# PLnew.net
KiCad netlist of a schematic drawn in EAGLE
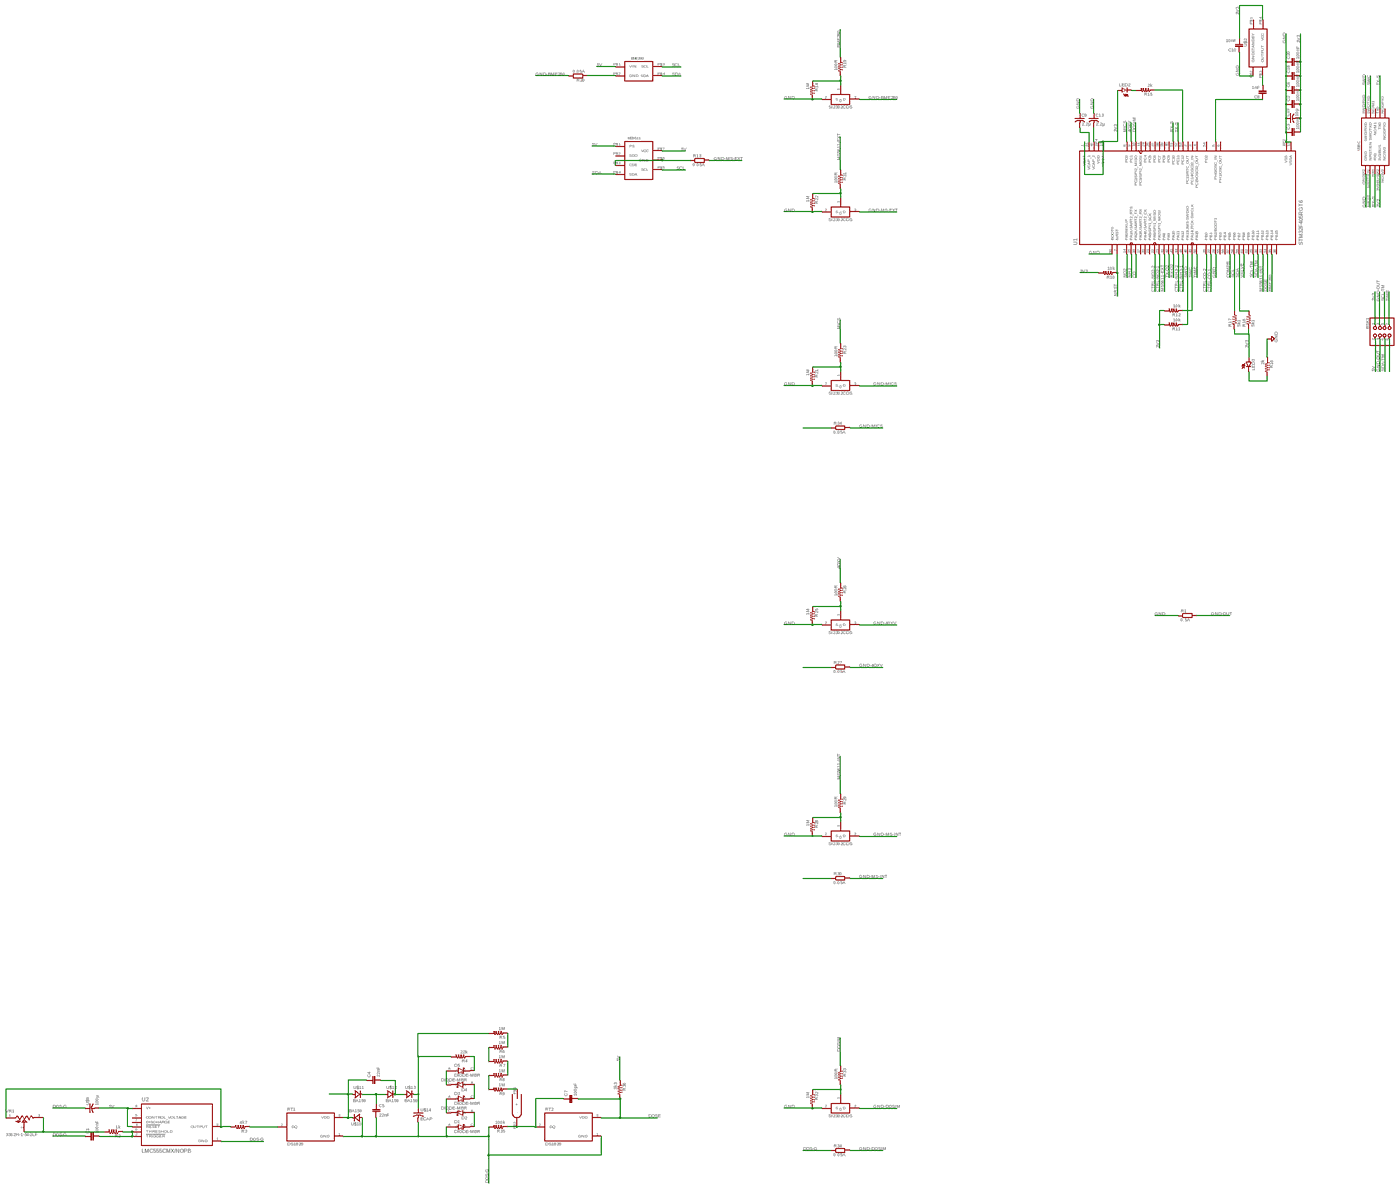
[diagram p0: schematic, sheet 1, overview]
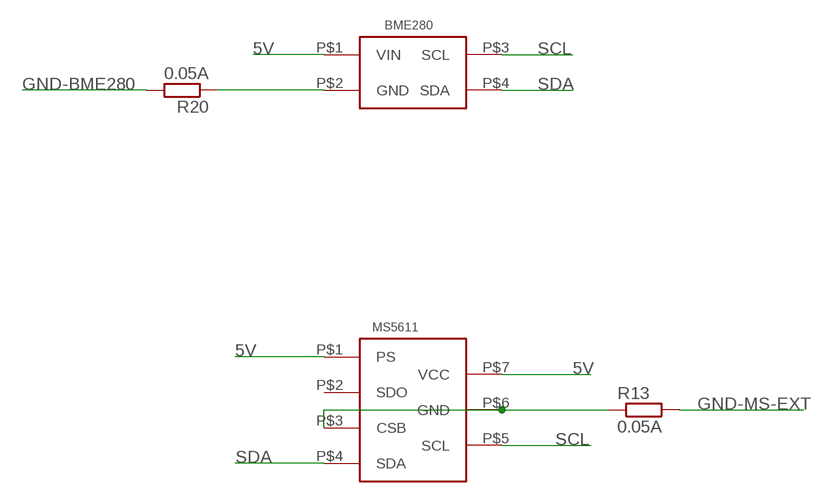
[diagram p1: schematic, sheet 1, part 1 of 4]
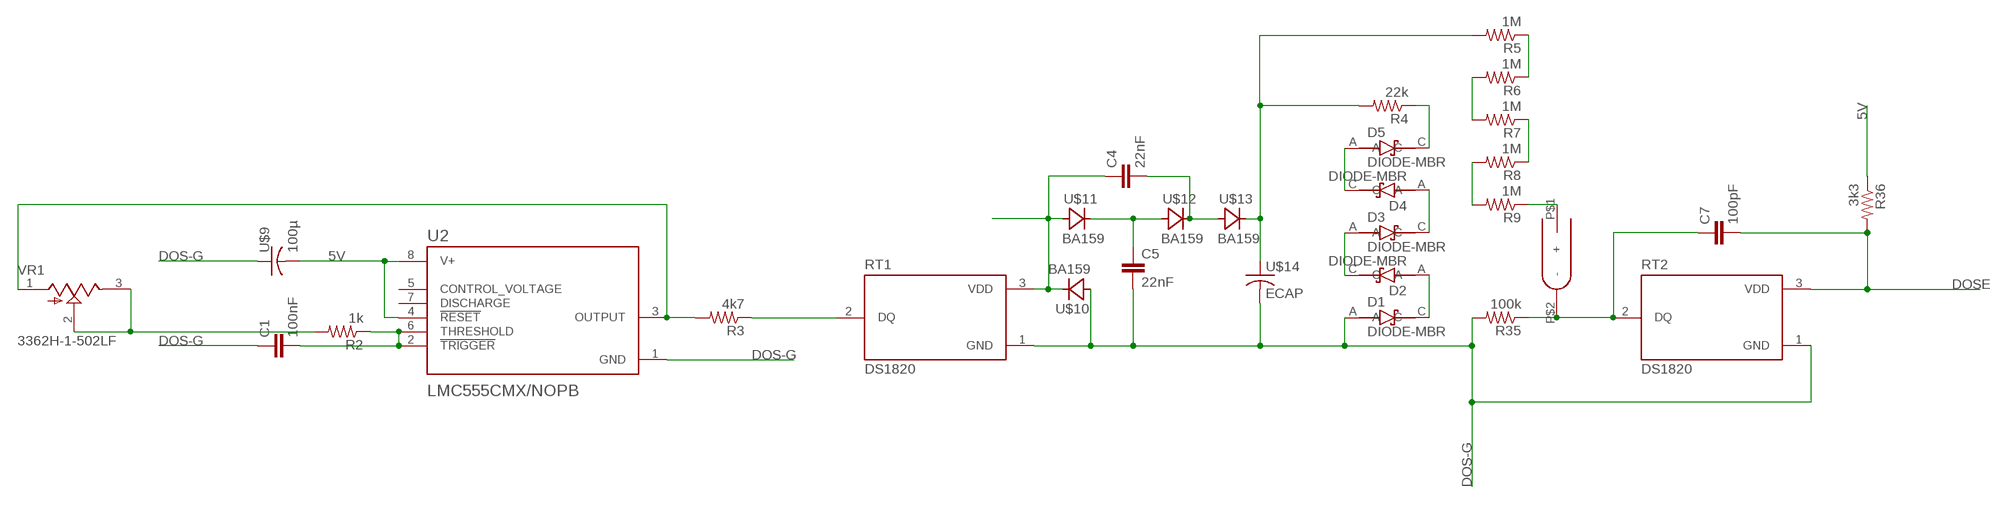
[diagram p2: schematic, sheet 1, part 2 of 4]
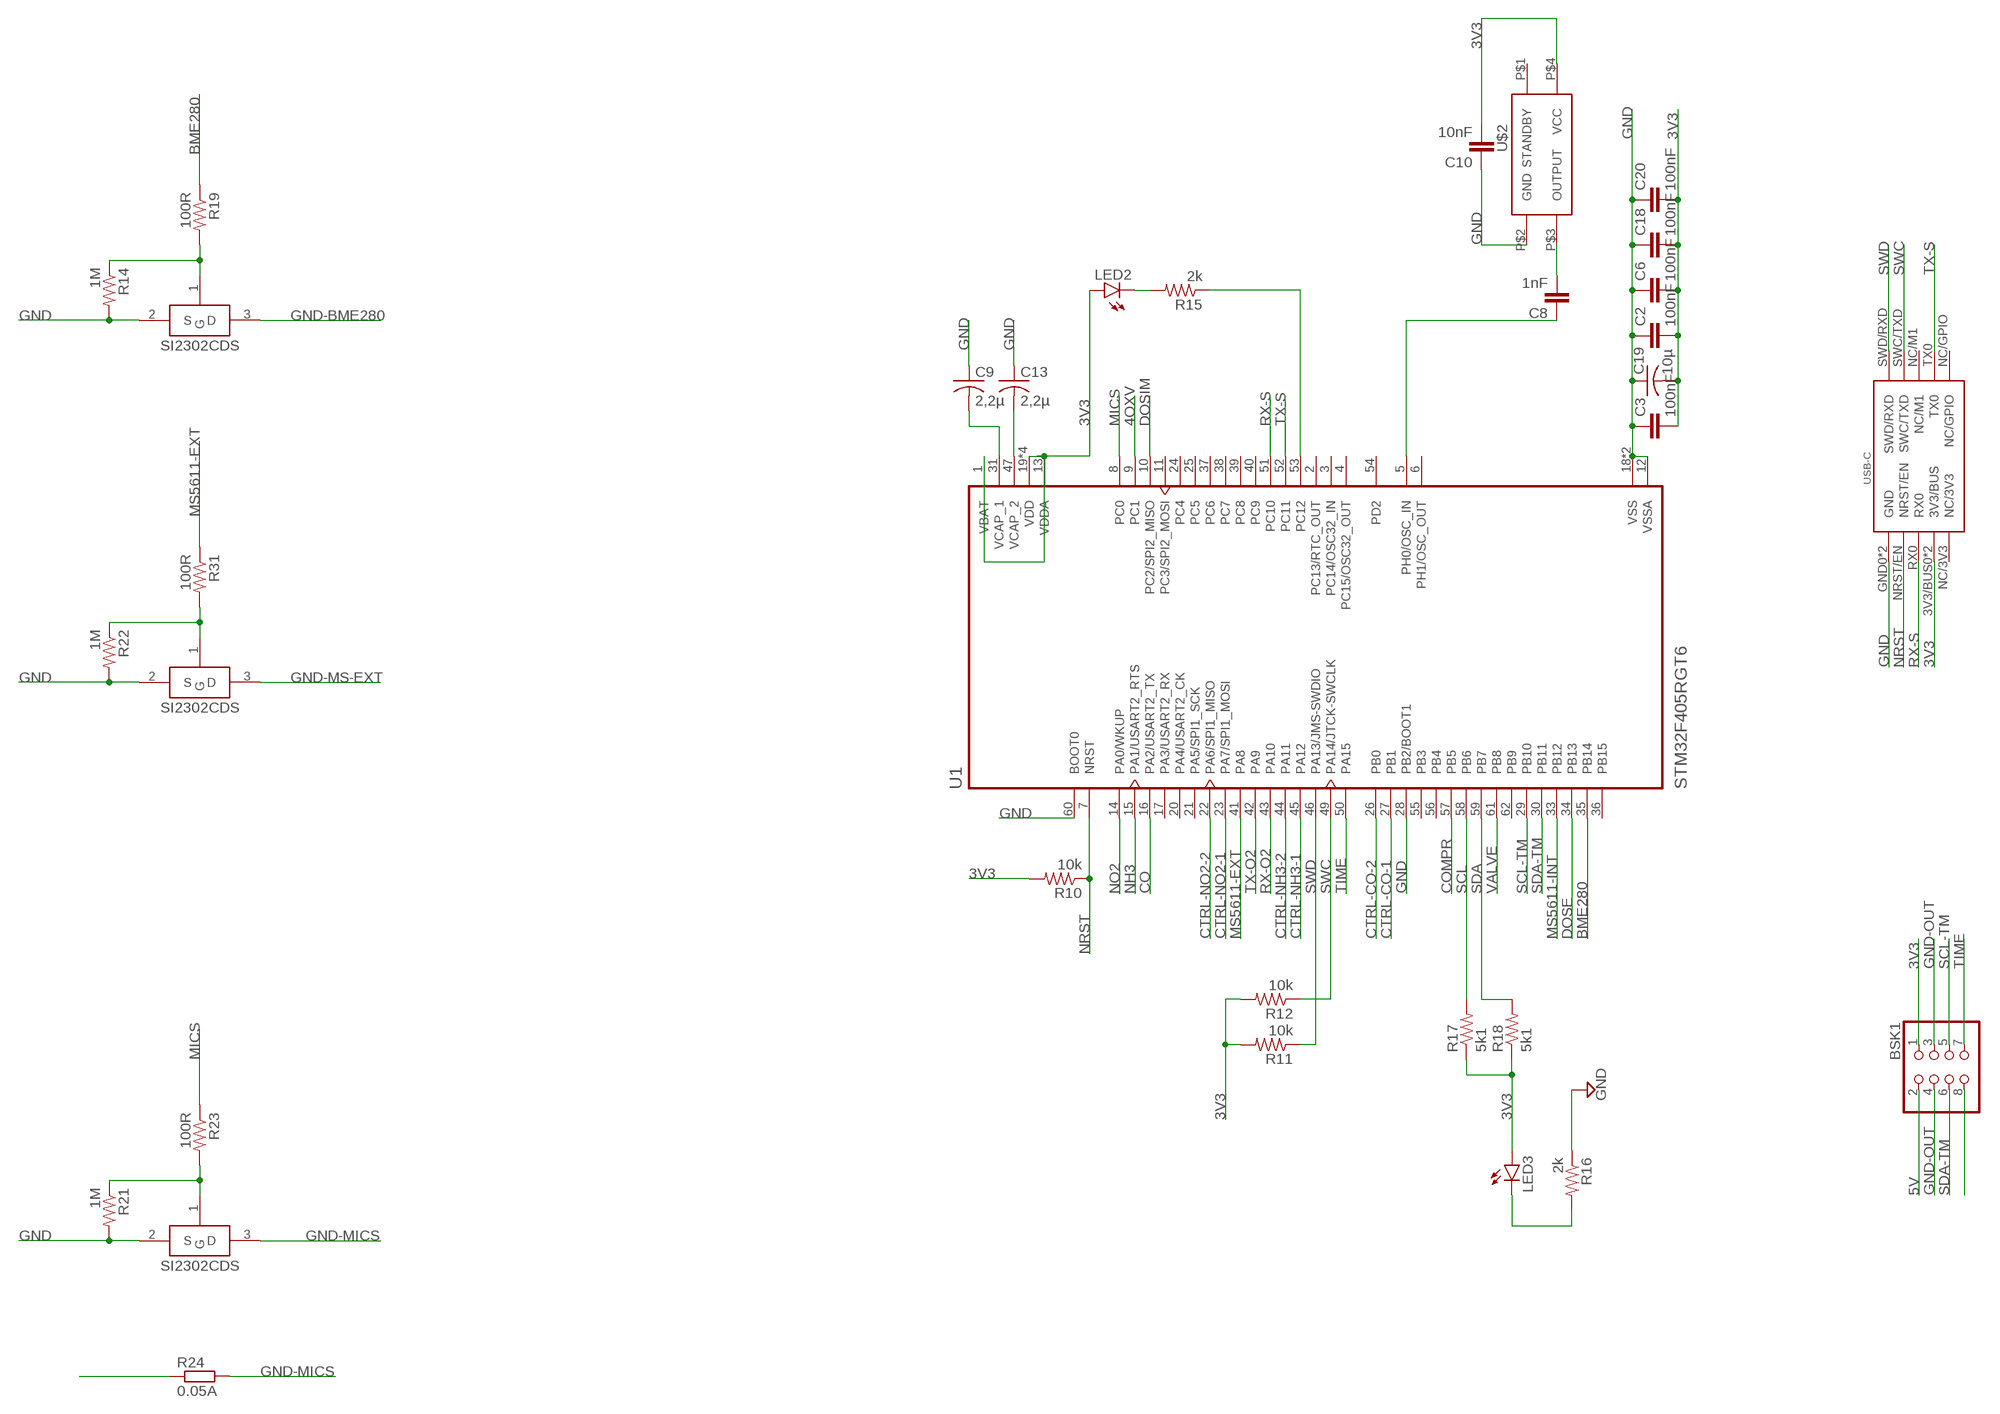
[diagram p3: schematic, sheet 1, part 3 of 4]
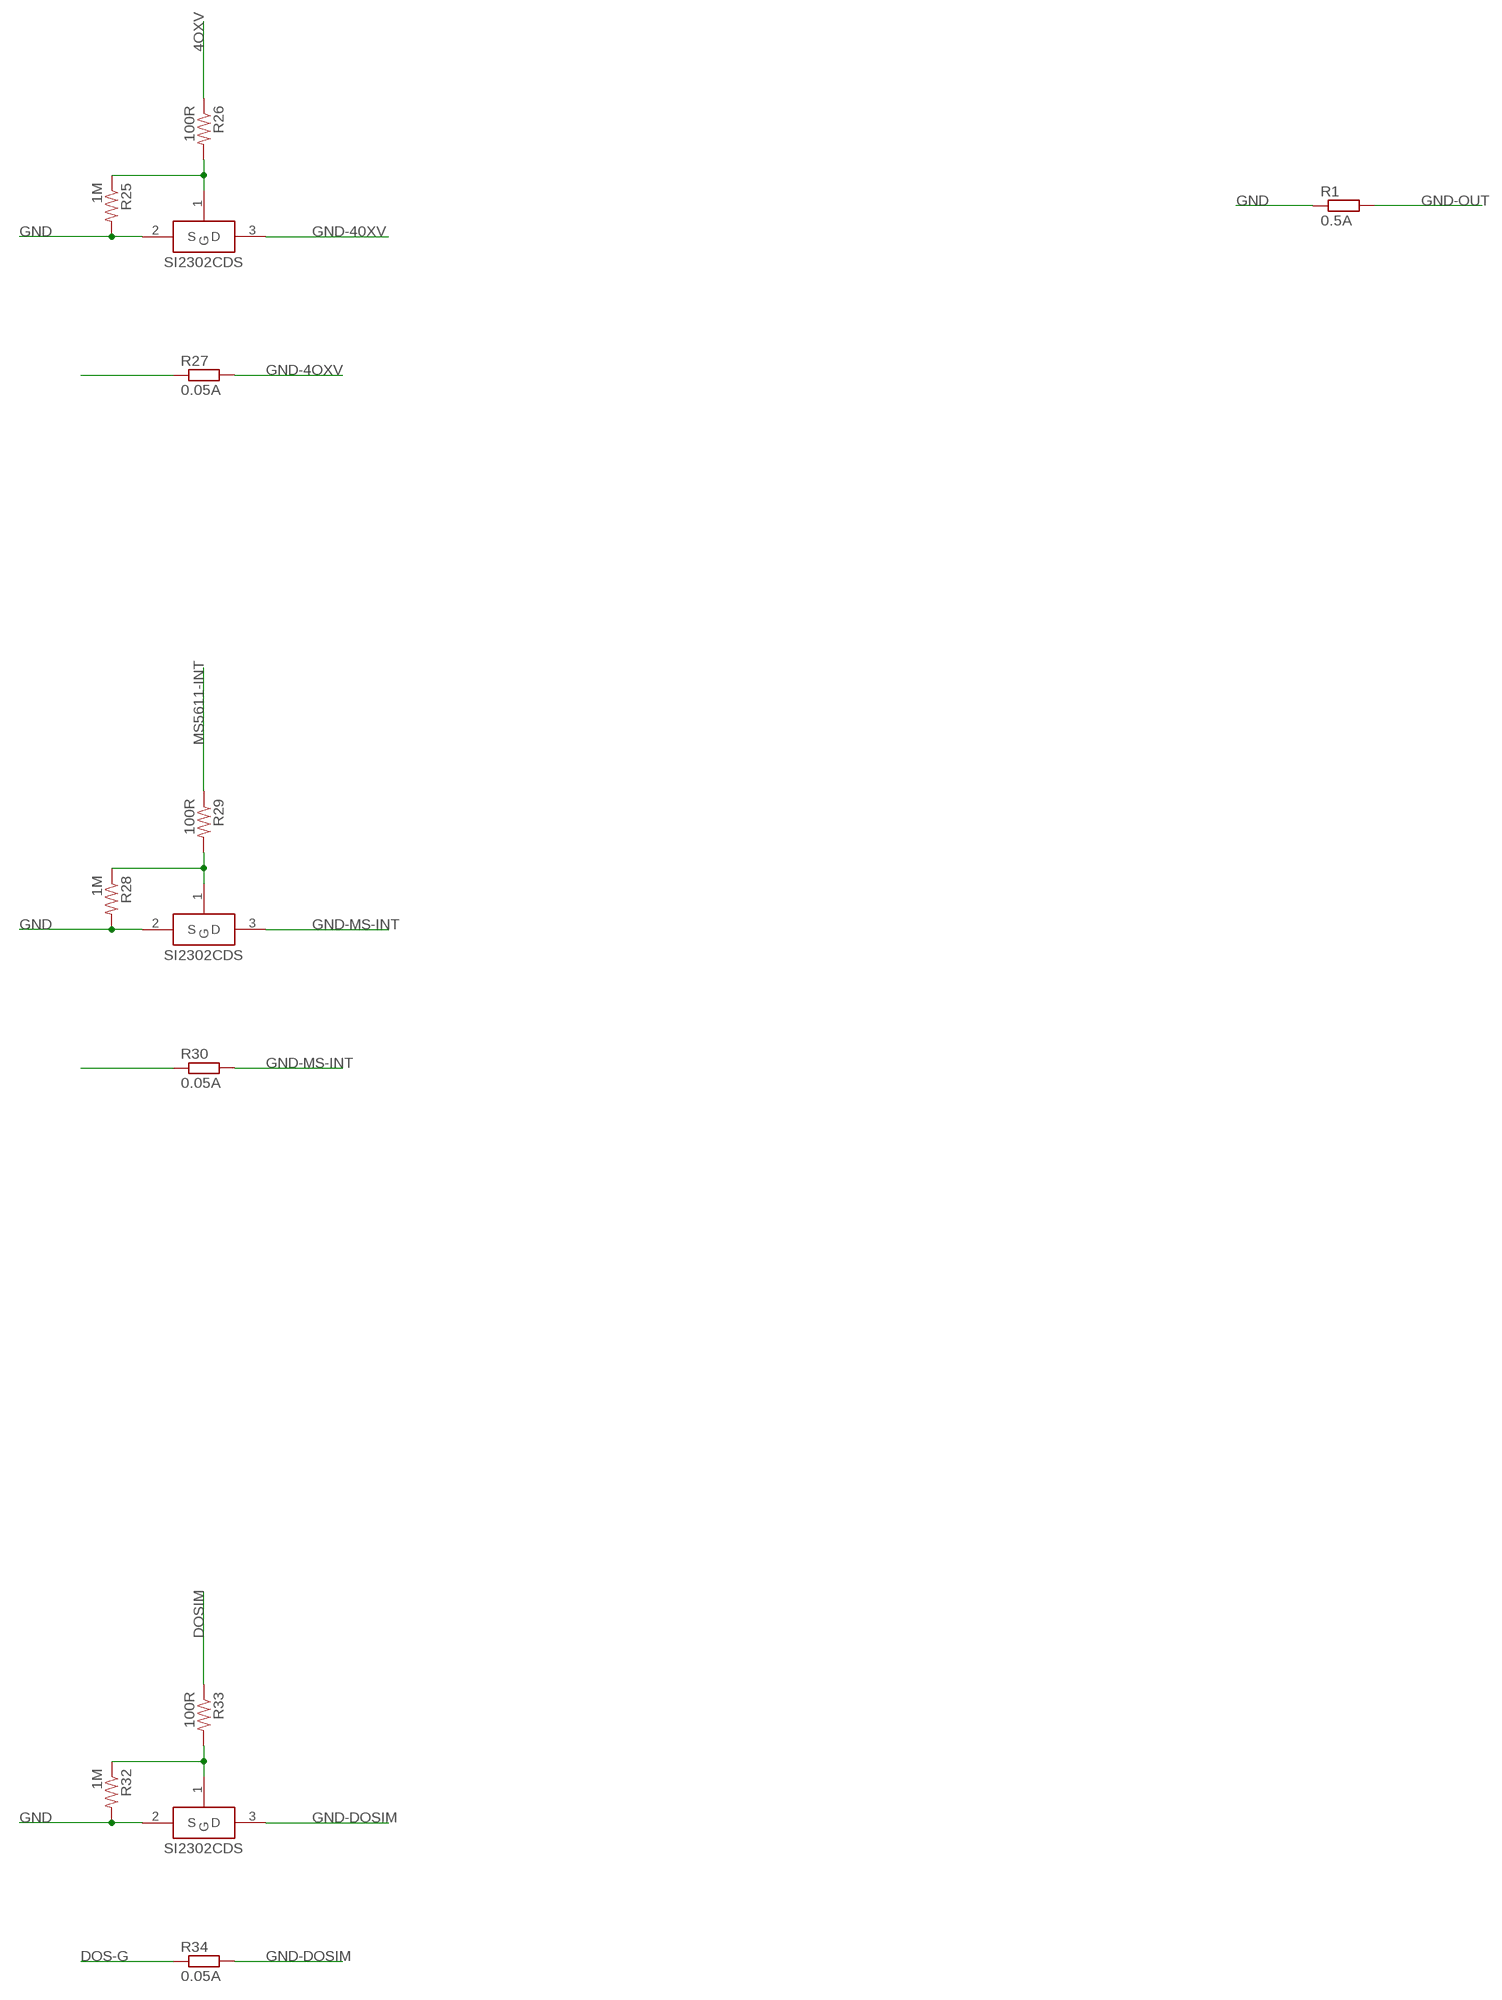
[diagram p4: schematic, sheet 1, part 4 of 4]

(export (version "E")
  (design (tool "Eeschema 10.0.6"))
  (components
    (comp (ref "BME280")
      (value "BME280")
      (footprint "eagle-import:BME280")
      (libsource (lib "eagle-import") (part "BME280"))
    )
    (comp (ref "BSK1")
      (value "PINHD-2X4")
      (footprint "eagle-import:2X04")
      (libsource (lib "eagle-import") (part "PINHD-2X4"))
    )
    (comp (ref "C1")
      (value "100nF")
      (footprint "eagle-import:C0603")
      (libsource (lib "eagle-import") (part "C-EUC0603"))
    )
    (comp (ref "C2")
      (value "100nF")
      (footprint "eagle-import:C0603")
      (libsource (lib "eagle-import") (part "C-EUC0603"))
    )
    (comp (ref "C3")
      (value "100nF")
      (footprint "eagle-import:C0603")
      (libsource (lib "eagle-import") (part "C-EUC0603"))
    )
    (comp (ref "C4")
      (value "22nF")
      (footprint "eagle-import:C1210")
      (libsource (lib "eagle-import") (part "C-EUC1210"))
    )
    (comp (ref "C5")
      (value "22nF")
      (footprint "eagle-import:C1210")
      (libsource (lib "eagle-import") (part "C-EUC1210"))
    )
    (comp (ref "C6")
      (value "100nF")
      (footprint "eagle-import:C0603")
      (libsource (lib "eagle-import") (part "C-EUC0603"))
    )
    (comp (ref "C7")
      (value "100pF")
      (footprint "eagle-import:C0603")
      (libsource (lib "eagle-import") (part "C-EUC0603"))
    )
    (comp (ref "C8")
      (value "1nF")
      (footprint "eagle-import:C0603")
      (libsource (lib "eagle-import") (part "C-EUC0603"))
    )
    (comp (ref "C9")
      (value "2,2µ")
      (footprint "eagle-import:C0603")
      (libsource (lib "eagle-import") (part "C-USC0603"))
    )
    (comp (ref "C10")
      (value "10nF")
      (footprint "eagle-import:C0603")
      (libsource (lib "eagle-import") (part "C-EUC0603"))
    )
    (comp (ref "C13")
      (value "2,2µ")
      (footprint "eagle-import:C0603")
      (libsource (lib "eagle-import") (part "C-USC0603"))
    )
    (comp (ref "C18")
      (value "100nF")
      (footprint "eagle-import:C0603")
      (libsource (lib "eagle-import") (part "C-EUC0603"))
    )
    (comp (ref "C19")
      (value "10µ")
      (footprint "eagle-import:C1206")
      (libsource (lib "eagle-import") (part "C-USC1206"))
    )
    (comp (ref "C20")
      (value "100nF")
      (footprint "eagle-import:C0603")
      (libsource (lib "eagle-import") (part "C-EUC0603"))
    )
    (comp (ref "D1")
      (value "DIODE-MBR")
      (footprint "eagle-import:SOD123")
      (fields (field (name "MF") "ON Semiconductor") (field (name "MP") "MBR0520LT1G"))
      (libsource (lib "eagle-import") (part "DIODE-MBR"))
    )
    (comp (ref "D2")
      (value "DIODE-MBR")
      (footprint "eagle-import:SOD123")
      (fields (field (name "MF") "ON Semiconductor") (field (name "MP") "MBR0520LT1G"))
      (libsource (lib "eagle-import") (part "DIODE-MBR"))
    )
    (comp (ref "D3")
      (value "DIODE-MBR")
      (footprint "eagle-import:SOD123")
      (fields (field (name "MF") "ON Semiconductor") (field (name "MP") "MBR0520LT1G"))
      (libsource (lib "eagle-import") (part "DIODE-MBR"))
    )
    (comp (ref "D4")
      (value "DIODE-MBR")
      (footprint "eagle-import:SOD123")
      (fields (field (name "MF") "ON Semiconductor") (field (name "MP") "MBR0520LT1G"))
      (libsource (lib "eagle-import") (part "DIODE-MBR"))
    )
    (comp (ref "D5")
      (value "DIODE-MBR")
      (footprint "eagle-import:SOD123")
      (fields (field (name "MF") "ON Semiconductor") (field (name "MP") "MBR0520LT1G"))
      (libsource (lib "eagle-import") (part "DIODE-MBR"))
    )
    (comp (ref "LED2")
      (value "LEDCHIPLED_0603")
      (footprint "eagle-import:CHIPLED_0603")
      (libsource (lib "eagle-import") (part "LEDCHIPLED_0603"))
    )
    (comp (ref "LED3")
      (value "LEDCHIPLED_0603")
      (footprint "eagle-import:CHIPLED_0603")
      (libsource (lib "eagle-import") (part "LEDCHIPLED_0603"))
    )
    (comp (ref "R1")
      (value "0.5A")
      (footprint "eagle-import:R1210")
      (libsource (lib "eagle-import") (part "R-EU_R1210"))
    )
    (comp (ref "R2")
      (value "1k")
      (footprint "eagle-import:R0603")
      (libsource (lib "eagle-import") (part "R-US_R0603"))
    )
    (comp (ref "R3")
      (value "4k7")
      (footprint "eagle-import:R0603")
      (libsource (lib "eagle-import") (part "R-US_R0603"))
    )
    (comp (ref "R4")
      (value "22k")
      (footprint "eagle-import:R0603")
      (libsource (lib "eagle-import") (part "R-US_R0603"))
    )
    (comp (ref "R5")
      (value "1M")
      (footprint "eagle-import:R0603")
      (libsource (lib "eagle-import") (part "R-US_R0603"))
    )
    (comp (ref "R6")
      (value "1M")
      (footprint "eagle-import:R0603")
      (libsource (lib "eagle-import") (part "R-US_R0603"))
    )
    (comp (ref "R7")
      (value "1M")
      (footprint "eagle-import:R0603")
      (libsource (lib "eagle-import") (part "R-US_R0603"))
    )
    (comp (ref "R8")
      (value "1M")
      (footprint "eagle-import:R0603")
      (libsource (lib "eagle-import") (part "R-US_R0603"))
    )
    (comp (ref "R9")
      (value "1M")
      (footprint "eagle-import:R0603")
      (libsource (lib "eagle-import") (part "R-US_R0603"))
    )
    (comp (ref "R10")
      (value "10k")
      (footprint "eagle-import:R0603")
      (libsource (lib "eagle-import") (part "R-US_R0603"))
    )
    (comp (ref "R11")
      (value "10k")
      (footprint "eagle-import:R0603")
      (libsource (lib "eagle-import") (part "R-US_R0603"))
    )
    (comp (ref "R12")
      (value "10k")
      (footprint "eagle-import:R0603")
      (libsource (lib "eagle-import") (part "R-US_R0603"))
    )
    (comp (ref "R13")
      (value "0.05A")
      (footprint "eagle-import:R1210")
      (libsource (lib "eagle-import") (part "R-EU_R1210"))
    )
    (comp (ref "R14")
      (value "1M")
      (footprint "eagle-import:R0603")
      (libsource (lib "eagle-import") (part "R-US_R0603"))
    )
    (comp (ref "R15")
      (value "2k")
      (footprint "eagle-import:R0603")
      (libsource (lib "eagle-import") (part "R-US_R0603"))
    )
    (comp (ref "R16")
      (value "2k")
      (footprint "eagle-import:R0603")
      (libsource (lib "eagle-import") (part "R-US_R0603"))
    )
    (comp (ref "R17")
      (value "5k1")
      (footprint "eagle-import:R0603")
      (libsource (lib "eagle-import") (part "R-US_R0603"))
    )
    (comp (ref "R18")
      (value "5k1")
      (footprint "eagle-import:R0603")
      (libsource (lib "eagle-import") (part "R-US_R0603"))
    )
    (comp (ref "R19")
      (value "100R")
      (footprint "eagle-import:R0603")
      (libsource (lib "eagle-import") (part "R-US_R0603"))
    )
    (comp (ref "R20")
      (value "0.05A")
      (footprint "eagle-import:R1210")
      (libsource (lib "eagle-import") (part "R-EU_R1210"))
    )
    (comp (ref "R21")
      (value "1M")
      (footprint "eagle-import:R0603")
      (libsource (lib "eagle-import") (part "R-US_R0603"))
    )
    (comp (ref "R22")
      (value "1M")
      (footprint "eagle-import:R0603")
      (libsource (lib "eagle-import") (part "R-US_R0603"))
    )
    (comp (ref "R23")
      (value "100R")
      (footprint "eagle-import:R0603")
      (libsource (lib "eagle-import") (part "R-US_R0603"))
    )
    (comp (ref "R24")
      (value "0.05A")
      (footprint "eagle-import:R1210")
      (libsource (lib "eagle-import") (part "R-EU_R1210"))
    )
    (comp (ref "R25")
      (value "1M")
      (footprint "eagle-import:R0603")
      (libsource (lib "eagle-import") (part "R-US_R0603"))
    )
    (comp (ref "R26")
      (value "100R")
      (footprint "eagle-import:R0603")
      (libsource (lib "eagle-import") (part "R-US_R0603"))
    )
    (comp (ref "R27")
      (value "0.05A")
      (footprint "eagle-import:R1210")
      (libsource (lib "eagle-import") (part "R-EU_R1210"))
    )
    (comp (ref "R28")
      (value "1M")
      (footprint "eagle-import:R0603")
      (libsource (lib "eagle-import") (part "R-US_R0603"))
    )
    (comp (ref "R29")
      (value "100R")
      (footprint "eagle-import:R0603")
      (libsource (lib "eagle-import") (part "R-US_R0603"))
    )
    (comp (ref "R30")
      (value "0.05A")
      (footprint "eagle-import:R1210")
      (libsource (lib "eagle-import") (part "R-EU_R1210"))
    )
    (comp (ref "R31")
      (value "100R")
      (footprint "eagle-import:R0603")
      (libsource (lib "eagle-import") (part "R-US_R0603"))
    )
    (comp (ref "R32")
      (value "1M")
      (footprint "eagle-import:R0603")
      (libsource (lib "eagle-import") (part "R-US_R0603"))
    )
    (comp (ref "R33")
      (value "100R")
      (footprint "eagle-import:R0603")
      (libsource (lib "eagle-import") (part "R-US_R0603"))
    )
    (comp (ref "R34")
      (value "0.05A")
      (footprint "eagle-import:R1210")
      (libsource (lib "eagle-import") (part "R-EU_R1210"))
    )
    (comp (ref "R35")
      (value "100k")
      (footprint "eagle-import:R0603")
      (libsource (lib "eagle-import") (part "R-US_R0603"))
    )
    (comp (ref "R36")
      (value "3k3")
      (footprint "eagle-import:R0603")
      (libsource (lib "eagle-import") (part "R-US_R0603"))
    )
    (comp (ref "RT1")
      (value "DS1820")
      (footprint "eagle-import:TO92_TO226")
      (fields (field (name "MF") "Maxim Integrated"))
      (libsource (lib "eagle-import") (part "DS1820"))
    )
    (comp (ref "RT2")
      (value "DS1820")
      (footprint "eagle-import:TO92_TO226")
      (fields (field (name "MF") "Maxim Integrated"))
      (libsource (lib "eagle-import") (part "DS1820"))
    )
    (comp (ref "U$1")
      (value "MS5611")
      (footprint "eagle-import:MS5611")
      (libsource (lib "eagle-import") (part "MS5611"))
    )
    (comp (ref "U$2")
      (value "Q24")
      (footprint "eagle-import:Q24")
      (libsource (lib "eagle-import") (part "Q24"))
    )
    (comp (ref "U$3")
      (value "SI2302CDS")
      (footprint "eagle-import:SOT23-3")
      (libsource (lib "eagle-import") (part "SI2302CDS"))
    )
    (comp (ref "U$4")
      (value "SI2302CDS")
      (footprint "eagle-import:SOT23-3")
      (libsource (lib "eagle-import") (part "SI2302CDS"))
    )
    (comp (ref "U$5")
      (value "SI2302CDS")
      (footprint "eagle-import:SOT23-3")
      (libsource (lib "eagle-import") (part "SI2302CDS"))
    )
    (comp (ref "U$6")
      (value "USB-C")
      (footprint "eagle-import:USB-C")
      (libsource (lib "eagle-import") (part "USB-C"))
    )
    (comp (ref "U$7")
      (value "SI2302CDS")
      (footprint "eagle-import:SOT23-3")
      (libsource (lib "eagle-import") (part "SI2302CDS"))
    )
    (comp (ref "U$8")
      (value "SI2302CDS")
      (footprint "eagle-import:SOT23-3")
      (libsource (lib "eagle-import") (part "SI2302CDS"))
    )
    (comp (ref "U$9")
      (value "100µ")
      (footprint "eagle-import:ECAP100-CMD")
      (libsource (lib "eagle-import") (part "ECAPECAP100"))
    )
    (comp (ref "U$10")
      (value "BA159")
      (footprint "eagle-import:BA159")
      (libsource (lib "eagle-import") (part "BA159"))
    )
    (comp (ref "U$11")
      (value "BA159")
      (footprint "eagle-import:BA159")
      (libsource (lib "eagle-import") (part "BA159"))
    )
    (comp (ref "U$12")
      (value "BA159")
      (footprint "eagle-import:BA159")
      (libsource (lib "eagle-import") (part "BA159"))
    )
    (comp (ref "U$13")
      (value "BA159")
      (footprint "eagle-import:BA159")
      (libsource (lib "eagle-import") (part "BA159"))
    )
    (comp (ref "U$14")
      (value "ECAP")
      (footprint "eagle-import:ECAP1MK")
      (libsource (lib "eagle-import") (part "ECAP"))
    )
    (comp (ref "U$15")
      (value "DOSIM")
      (footprint "eagle-import:DOSIM")
      (libsource (lib "eagle-import") (part "DOSIM"))
    )
    (comp (ref "U$19")
      (value "SI2302CDS")
      (footprint "eagle-import:SOT23-3")
      (libsource (lib "eagle-import") (part "SI2302CDS"))
    )
    (comp (ref "U1")
      (value "STM32F405RGT6")
      (footprint "eagle-import:QFP50P1200X1200X160-64N")
      (fields (field (name "DIGI-KEY_PART_NUMBER") "497-11767-ND") (field (name "MF") "STMicroelectronics"))
      (libsource (lib "eagle-import") (part "STM32F405RGT6"))
    )
    (comp (ref "U2")
      (value "LMC555CMX/NOPB")
      (footprint "eagle-import:SOIC127P599X175-8N")
      (fields (field (name "MF") "Texas Instruments"))
      (libsource (lib "eagle-import") (part "LMC555CMX/NOPB"))
    )
    (comp (ref "VR1")
      (value "3362H-1-502LF")
      (footprint "eagle-import:TRIM_3362H-1-502LF")
      (fields (field (name "MF") "Bourns") (field (name "MP") "3362P-1-502LF"))
      (libsource (lib "eagle-import") (part "3362H-1-502LF"))
    )
  )
  (nets
    (net (code "1") (name "/3V3") (class "Default")
      (node (ref "BSK1") (pin "1") (pinfunction "1_1") (pintype "passive"))
      (node (ref "C10") (pin "2") (pinfunction "2_2") (pintype "passive"))
      (node (ref "C18") (pin "2") (pinfunction "2_2") (pintype "passive"))
      (node (ref "C19") (pin "2") (pinfunction "2_2") (pintype "passive"))
      (node (ref "C2") (pin "2") (pinfunction "2_2") (pintype "passive"))
      (node (ref "C20") (pin "2") (pinfunction "2_2") (pintype "passive"))
      (node (ref "C3") (pin "2") (pinfunction "2_2") (pintype "passive"))
      (node (ref "C6") (pin "2") (pinfunction "2_2") (pintype "passive"))
      (node (ref "LED2") (pin "A") (pinfunction "A_A") (pintype "passive"))
      (node (ref "LED3") (pin "A") (pinfunction "A_A") (pintype "passive"))
      (node (ref "R10") (pin "2") (pinfunction "2_2") (pintype "passive"))
      (node (ref "R11") (pin "2") (pinfunction "2_2") (pintype "passive"))
      (node (ref "R12") (pin "2") (pinfunction "2_2") (pintype "passive"))
      (node (ref "R17") (pin "1") (pinfunction "1_1") (pintype "passive"))
      (node (ref "R18") (pin "1") (pinfunction "1_1") (pintype "passive"))
      (node (ref "U$2") (pin "P$4") (pinfunction "VCC_P$4") (pintype "bidirectional"))
      (node (ref "U$6") (pin "3V3/BUS0") (pinfunction "3V3/BUS_3V3/BUS0") (pintype "bidirectional"))
      (node (ref "U$6") (pin "3V3/BUS1") (pinfunction "3V3/BUS_3V3/BUS1") (pintype "bidirectional"))
      (node (ref "U1") (pin "1") (pinfunction "VBAT_1") (pintype "power_in"))
      (node (ref "U1") (pin "13") (pinfunction "VDDA_13") (pintype "power_in"))
      (node (ref "U1") (pin "19") (pinfunction "VDD_19") (pintype "power_in"))
      (node (ref "U1") (pin "32") (pinfunction "VDD_32") (pintype "power_in"))
      (node (ref "U1") (pin "48") (pinfunction "VDD_48") (pintype "power_in"))
      (node (ref "U1") (pin "64") (pinfunction "VDD_64") (pintype "power_in"))
    )
    (net (code "2") (name "/4OXV") (class "Default")
      (node (ref "R26") (pin "1") (pinfunction "1_1") (pintype "passive"))
      (node (ref "U1") (pin "9") (pinfunction "PC1_9") (pintype "bidirectional"))
    )
    (net (code "3") (name "/5V") (class "Default")
      (node (ref "BME280") (pin "P$1") (pinfunction "VIN_P$1") (pintype "bidirectional"))
      (node (ref "BSK1") (pin "2") (pinfunction "2_2") (pintype "passive"))
      (node (ref "R36") (pin "1") (pinfunction "1_1") (pintype "passive"))
      (node (ref "U$1") (pin "P$1") (pinfunction "PS_P$1") (pintype "bidirectional"))
      (node (ref "U$1") (pin "P$7") (pinfunction "VCC_P$7") (pintype "bidirectional"))
      (node (ref "U$9") (pin "P$2") (pinfunction "2_P$2") (pintype "passive"))
      (node (ref "U2") (pin "4") (pinfunction "~{RESET}_4") (pintype "input"))
      (node (ref "U2") (pin "8") (pinfunction "V+_8") (pintype "power_in"))
    )
    (net (code "4") (name "/BME280") (class "Default")
      (node (ref "R19") (pin "1") (pinfunction "1_1") (pintype "passive"))
      (node (ref "U1") (pin "35") (pinfunction "PB14_35") (pintype "bidirectional"))
    )
    (net (code "5") (name "/CO") (class "Default")
      (node (ref "U1") (pin "16") (pinfunction "PA2/USART2_TX_16") (pintype "bidirectional"))
    )
    (net (code "6") (name "/COMPR") (class "Default")
      (node (ref "U1") (pin "57") (pinfunction "PB5_57") (pintype "bidirectional"))
    )
    (net (code "7") (name "/CTRL-CO-1") (class "Default")
      (node (ref "U1") (pin "27") (pinfunction "PB1_27") (pintype "bidirectional"))
    )
    (net (code "8") (name "/CTRL-CO-2") (class "Default")
      (node (ref "U1") (pin "26") (pinfunction "PB0_26") (pintype "bidirectional"))
    )
    (net (code "9") (name "/CTRL-NH3-1") (class "Default")
      (node (ref "U1") (pin "45") (pinfunction "PA12_45") (pintype "bidirectional"))
    )
    (net (code "10") (name "/CTRL-NH3-2") (class "Default")
      (node (ref "U1") (pin "44") (pinfunction "PA11_44") (pintype "bidirectional"))
    )
    (net (code "11") (name "/CTRL-NO2-1") (class "Default")
      (node (ref "U1") (pin "23") (pinfunction "PA7/SPI1_MOSI_23") (pintype "bidirectional"))
    )
    (net (code "12") (name "/CTRL-NO2-2") (class "Default")
      (node (ref "U1") (pin "22") (pinfunction "PA6/SPI1_MISO_22") (pintype "bidirectional"))
    )
    (net (code "13") (name "/DOS-G") (class "Default")
      (node (ref "C1") (pin "1") (pinfunction "1_1") (pintype "passive"))
      (node (ref "C5") (pin "2") (pinfunction "2_2") (pintype "passive"))
      (node (ref "D1") (pin "A") (pinfunction "A_A") (pintype "passive"))
      (node (ref "R34") (pin "1") (pinfunction "1_1") (pintype "passive"))
      (node (ref "R35") (pin "2") (pinfunction "2_2") (pintype "passive"))
      (node (ref "RT1") (pin "1") (pinfunction "GND_1") (pintype "power_in"))
      (node (ref "RT2") (pin "1") (pinfunction "GND_1") (pintype "power_in"))
      (node (ref "U$10") (pin "P$1") (pinfunction "A_P$1") (pintype "passive"))
      (node (ref "U$14") (pin "P$2") (pinfunction "2_P$2") (pintype "passive"))
      (node (ref "U$9") (pin "P$1") (pinfunction "1_P$1") (pintype "passive"))
      (node (ref "U2") (pin "1") (pinfunction "GND_1") (pintype "power_in"))
    )
    (net (code "14") (name "/DOSE") (class "Default")
      (node (ref "C7") (pin "2") (pinfunction "2_2") (pintype "passive"))
      (node (ref "R36") (pin "2") (pinfunction "2_2") (pintype "passive"))
      (node (ref "RT2") (pin "3") (pinfunction "VDD_3") (pintype "power_in"))
      (node (ref "U1") (pin "34") (pinfunction "PB13_34") (pintype "bidirectional"))
    )
    (net (code "15") (name "/DOSIM") (class "Default")
      (node (ref "R33") (pin "1") (pinfunction "1_1") (pintype "passive"))
      (node (ref "U1") (pin "10") (pinfunction "PC2/SPI2_MISO_10") (pintype "bidirectional"))
    )
    (net (code "16") (name "/GND-4OXV") (class "Default")
      (node (ref "R27") (pin "2") (pinfunction "2_2") (pintype "passive"))
    )
    (net (code "17") (name "/GND-40XV") (class "Default")
      (node (ref "U$5") (pin "3") (pinfunction "D_3") (pintype "bidirectional"))
    )
    (net (code "18") (name "/GND-BME280") (class "Default")
      (node (ref "R20") (pin "2") (pinfunction "2_2") (pintype "passive"))
      (node (ref "U$3") (pin "3") (pinfunction "D_3") (pintype "bidirectional"))
    )
    (net (code "19") (name "/GND-DOSIM") (class "Default")
      (node (ref "R34") (pin "2") (pinfunction "2_2") (pintype "passive"))
      (node (ref "U$8") (pin "3") (pinfunction "D_3") (pintype "bidirectional"))
    )
    (net (code "20") (name "/GND-MICS") (class "Default")
      (node (ref "R24") (pin "2") (pinfunction "2_2") (pintype "passive"))
      (node (ref "U$4") (pin "3") (pinfunction "D_3") (pintype "bidirectional"))
    )
    (net (code "21") (name "/GND-MS-EXT") (class "Default")
      (node (ref "R13") (pin "2") (pinfunction "2_2") (pintype "passive"))
      (node (ref "U$19") (pin "3") (pinfunction "D_3") (pintype "bidirectional"))
    )
    (net (code "22") (name "/GND-MS-INT") (class "Default")
      (node (ref "R30") (pin "2") (pinfunction "2_2") (pintype "passive"))
      (node (ref "U$7") (pin "3") (pinfunction "D_3") (pintype "bidirectional"))
    )
    (net (code "23") (name "/GND-OUT") (class "Default")
      (node (ref "BSK1") (pin "3") (pinfunction "3_3") (pintype "passive"))
      (node (ref "BSK1") (pin "4") (pinfunction "4_4") (pintype "passive"))
      (node (ref "R1") (pin "2") (pinfunction "2_2") (pintype "passive"))
    )
    (net (code "24") (name "/MICS") (class "Default")
      (node (ref "R23") (pin "1") (pinfunction "1_1") (pintype "passive"))
      (node (ref "U1") (pin "8") (pinfunction "PC0_8") (pintype "bidirectional"))
    )
    (net (code "25") (name "/MS5611-EXT") (class "Default")
      (node (ref "R31") (pin "1") (pinfunction "1_1") (pintype "passive"))
      (node (ref "U1") (pin "41") (pinfunction "PA8_41") (pintype "bidirectional"))
    )
    (net (code "26") (name "/MS5611-INT") (class "Default")
      (node (ref "R29") (pin "1") (pinfunction "1_1") (pintype "passive"))
      (node (ref "U1") (pin "33") (pinfunction "PB12_33") (pintype "bidirectional"))
    )
    (net (code "27") (name "/NH3") (class "Default")
      (node (ref "U1") (pin "15") (pinfunction "PA1/USART2_RTS_15") (pintype "bidirectional"))
    )
    (net (code "28") (name "/NO2") (class "Default")
      (node (ref "U1") (pin "14") (pinfunction "PA0/WKUP_14") (pintype "bidirectional"))
    )
    (net (code "29") (name "/NRST") (class "Default")
      (node (ref "R10") (pin "1") (pinfunction "1_1") (pintype "passive"))
      (node (ref "U$6") (pin "NRST/EN") (pinfunction "NRST/EN_NRST/EN") (pintype "bidirectional"))
      (node (ref "U1") (pin "7") (pinfunction "NRST_7") (pintype "bidirectional"))
    )
    (net (code "30") (name "/RX-O2") (class "Default")
      (node (ref "U1") (pin "43") (pinfunction "PA10_43") (pintype "bidirectional"))
    )
    (net (code "31") (name "/RX-S") (class "Default")
      (node (ref "U$6") (pin "RX0") (pinfunction "RX0_RX0") (pintype "bidirectional"))
      (node (ref "U1") (pin "51") (pinfunction "PC10_51") (pintype "bidirectional"))
    )
    (net (code "32") (name "/SCL") (class "Default")
      (node (ref "BME280") (pin "P$3") (pinfunction "SCL_P$3") (pintype "bidirectional"))
      (node (ref "R17") (pin "2") (pinfunction "2_2") (pintype "passive"))
      (node (ref "U$1") (pin "P$5") (pinfunction "SCL_P$5") (pintype "bidirectional"))
      (node (ref "U1") (pin "58") (pinfunction "PB6_58") (pintype "bidirectional"))
    )
    (net (code "33") (name "/SCL-TM") (class "Default")
      (node (ref "BSK1") (pin "5") (pinfunction "5_5") (pintype "passive"))
      (node (ref "U1") (pin "29") (pinfunction "PB10_29") (pintype "bidirectional"))
    )
    (net (code "34") (name "/SDA") (class "Default")
      (node (ref "BME280") (pin "P$4") (pinfunction "SDA_P$4") (pintype "bidirectional"))
      (node (ref "R18") (pin "2") (pinfunction "2_2") (pintype "passive"))
      (node (ref "U$1") (pin "P$4") (pinfunction "SDA_P$4") (pintype "bidirectional"))
      (node (ref "U1") (pin "59") (pinfunction "PB7_59") (pintype "bidirectional"))
    )
    (net (code "35") (name "/SDA-TM") (class "Default")
      (node (ref "BSK1") (pin "6") (pinfunction "6_6") (pintype "passive"))
      (node (ref "U1") (pin "30") (pinfunction "PB11_30") (pintype "bidirectional"))
    )
    (net (code "36") (name "/SWC") (class "Default")
      (node (ref "R12") (pin "1") (pinfunction "1_1") (pintype "passive"))
      (node (ref "U$6") (pin "SWC/TXD") (pinfunction "SWC/TXD_SWC/TXD") (pintype "bidirectional"))
      (node (ref "U1") (pin "49") (pinfunction "PA14/JTCK-SWCLK_49") (pintype "bidirectional"))
    )
    (net (code "37") (name "/SWD") (class "Default")
      (node (ref "R11") (pin "1") (pinfunction "1_1") (pintype "passive"))
      (node (ref "U$6") (pin "SWD/RXD") (pinfunction "SWD/RXD_SWD/RXD") (pintype "bidirectional"))
      (node (ref "U1") (pin "46") (pinfunction "PA13/JMS-SWDIO_46") (pintype "bidirectional"))
    )
    (net (code "38") (name "/TIME") (class "Default")
      (node (ref "BSK1") (pin "7") (pinfunction "7_7") (pintype "passive"))
      (node (ref "U1") (pin "50") (pinfunction "PA15_50") (pintype "bidirectional"))
    )
    (net (code "39") (name "/TX-O2") (class "Default")
      (node (ref "U1") (pin "42") (pinfunction "PA9_42") (pintype "bidirectional"))
    )
    (net (code "40") (name "/TX-S") (class "Default")
      (node (ref "U$6") (pin "TX0") (pinfunction "TX0_TX0") (pintype "bidirectional"))
      (node (ref "U1") (pin "52") (pinfunction "PC11_52") (pintype "bidirectional"))
    )
    (net (code "41") (name "/VALVE") (class "Default")
      (node (ref "U1") (pin "61") (pinfunction "PB8_61") (pintype "bidirectional"))
    )
    (net (code "42") (name "GND") (class "Default")
      (node (ref "C10") (pin "1") (pinfunction "1_1") (pintype "passive"))
      (node (ref "C13") (pin "1") (pinfunction "1_1") (pintype "passive"))
      (node (ref "C18") (pin "1") (pinfunction "1_1") (pintype "passive"))
      (node (ref "C19") (pin "1") (pinfunction "1_1") (pintype "passive"))
      (node (ref "C2") (pin "1") (pinfunction "1_1") (pintype "passive"))
      (node (ref "C20") (pin "1") (pinfunction "1_1") (pintype "passive"))
      (node (ref "C3") (pin "1") (pinfunction "1_1") (pintype "passive"))
      (node (ref "C6") (pin "1") (pinfunction "1_1") (pintype "passive"))
      (node (ref "C9") (pin "1") (pinfunction "1_1") (pintype "passive"))
      (node (ref "R1") (pin "1") (pinfunction "1_1") (pintype "passive"))
      (node (ref "R14") (pin "2") (pinfunction "2_2") (pintype "passive"))
      (node (ref "R16") (pin "1") (pinfunction "1_1") (pintype "passive"))
      (node (ref "R21") (pin "2") (pinfunction "2_2") (pintype "passive"))
      (node (ref "R22") (pin "2") (pinfunction "2_2") (pintype "passive"))
      (node (ref "R25") (pin "2") (pinfunction "2_2") (pintype "passive"))
      (node (ref "R28") (pin "2") (pinfunction "2_2") (pintype "passive"))
      (node (ref "R32") (pin "2") (pinfunction "2_2") (pintype "passive"))
      (node (ref "U$19") (pin "2") (pinfunction "S_2") (pintype "bidirectional"))
      (node (ref "U$2") (pin "P$2") (pinfunction "GND_P$2") (pintype "bidirectional"))
      (node (ref "U$3") (pin "2") (pinfunction "S_2") (pintype "bidirectional"))
      (node (ref "U$4") (pin "2") (pinfunction "S_2") (pintype "bidirectional"))
      (node (ref "U$5") (pin "2") (pinfunction "S_2") (pintype "bidirectional"))
      (node (ref "U$6") (pin "GND0") (pinfunction "GND_GND0") (pintype "bidirectional"))
      (node (ref "U$6") (pin "GND1") (pinfunction "GND_GND1") (pintype "bidirectional"))
      (node (ref "U$7") (pin "2") (pinfunction "S_2") (pintype "bidirectional"))
      (node (ref "U$8") (pin "2") (pinfunction "S_2") (pintype "bidirectional"))
      (node (ref "U1") (pin "12") (pinfunction "VSSA_12") (pintype "power_in"))
      (node (ref "U1") (pin "18") (pinfunction "VSS_18") (pintype "power_in"))
      (node (ref "U1") (pin "28") (pinfunction "PB2/BOOT1_28") (pintype "bidirectional"))
      (node (ref "U1") (pin "60") (pinfunction "BOOT0_60") (pintype "bidirectional"))
      (node (ref "U1") (pin "63") (pinfunction "VSS_63") (pintype "power_in"))
    )
    (net (code "43") (name "Net-(BME280-GND)") (class "Default")
      (node (ref "BME280") (pin "P$2") (pinfunction "GND_P$2") (pintype "bidirectional"))
      (node (ref "R20") (pin "1") (pinfunction "1_1") (pintype "passive"))
    )
    (net (code "44") (name "Net-(D1-PadC)") (class "Default")
      (node (ref "D1") (pin "C") (pinfunction "C_C") (pintype "passive"))
      (node (ref "D2") (pin "A") (pinfunction "A_A") (pintype "passive"))
    )
    (net (code "45") (name "Net-(D2-PadC)") (class "Default")
      (node (ref "D2") (pin "C") (pinfunction "C_C") (pintype "passive"))
      (node (ref "D3") (pin "A") (pinfunction "A_A") (pintype "passive"))
    )
    (net (code "46") (name "Net-(D3-PadC)") (class "Default")
      (node (ref "D3") (pin "C") (pinfunction "C_C") (pintype "passive"))
      (node (ref "D4") (pin "A") (pinfunction "A_A") (pintype "passive"))
    )
    (net (code "47") (name "Net-(D4-PadC)") (class "Default")
      (node (ref "D4") (pin "C") (pinfunction "C_C") (pintype "passive"))
      (node (ref "D5") (pin "A") (pinfunction "A_A") (pintype "passive"))
    )
    (net (code "48") (name "Net-(D5-PadC)") (class "Default")
      (node (ref "D5") (pin "C") (pinfunction "C_C") (pintype "passive"))
      (node (ref "R4") (pin "1") (pinfunction "1_1") (pintype "passive"))
    )
    (net (code "49") (name "Net-(LED2-PadC)") (class "Default")
      (node (ref "LED2") (pin "C") (pinfunction "C_C") (pintype "passive"))
      (node (ref "R15") (pin "2") (pinfunction "2_2") (pintype "passive"))
    )
    (net (code "50") (name "Net-(LED3-PadC)") (class "Default")
      (node (ref "LED3") (pin "C") (pinfunction "C_C") (pintype "passive"))
      (node (ref "R16") (pin "2") (pinfunction "2_2") (pintype "passive"))
    )
    (net (code "51") (name "Net-(R5-Pad1)") (class "Default")
      (node (ref "R5") (pin "1") (pinfunction "1_1") (pintype "passive"))
      (node (ref "R6") (pin "1") (pinfunction "1_1") (pintype "passive"))
    )
    (net (code "52") (name "Net-(R6-Pad2)") (class "Default")
      (node (ref "R6") (pin "2") (pinfunction "2_2") (pintype "passive"))
      (node (ref "R7") (pin "2") (pinfunction "2_2") (pintype "passive"))
    )
    (net (code "53") (name "Net-(R7-Pad1)") (class "Default")
      (node (ref "R7") (pin "1") (pinfunction "1_1") (pintype "passive"))
      (node (ref "R8") (pin "1") (pinfunction "1_1") (pintype "passive"))
    )
    (net (code "54") (name "Net-(R8-Pad2)") (class "Default")
      (node (ref "R8") (pin "2") (pinfunction "2_2") (pintype "passive"))
      (node (ref "R9") (pin "2") (pinfunction "2_2") (pintype "passive"))
    )
    (net (code "55") (name "Net-(RT1-DQ)") (class "Default")
      (node (ref "R3") (pin "1") (pinfunction "1_1") (pintype "passive"))
      (node (ref "RT1") (pin "2") (pinfunction "DQ_2") (pintype "bidirectional"))
    )
    (net (code "56") (name "Net-(RT1-VDD)") (class "Default")
      (node (ref "C4") (pin "1") (pinfunction "1_1") (pintype "passive"))
      (node (ref "RT1") (pin "3") (pinfunction "VDD_3") (pintype "power_in"))
      (node (ref "U$10") (pin "P$2") (pinfunction "C_P$2") (pintype "passive"))
      (node (ref "U$11") (pin "P$1") (pinfunction "A_P$1") (pintype "passive"))
    )
    (net (code "57") (name "Net-(RT2-DQ)") (class "Default")
      (node (ref "C7") (pin "1") (pinfunction "1_1") (pintype "passive"))
      (node (ref "R35") (pin "1") (pinfunction "1_1") (pintype "passive"))
      (node (ref "RT2") (pin "2") (pinfunction "DQ_2") (pintype "bidirectional"))
      (node (ref "U$15") (pin "P$2") (pinfunction "-_P$2") (pintype "bidirectional"))
    )
    (net (code "58") (name "Net-(U$1-CSB)") (class "Default")
      (node (ref "R13") (pin "1") (pinfunction "1_1") (pintype "passive"))
      (node (ref "U$1") (pin "P$3") (pinfunction "CSB_P$3") (pintype "bidirectional"))
      (node (ref "U$1") (pin "P$6") (pinfunction "GND_P$6") (pintype "bidirectional"))
    )
    (net (code "59") (name "Net-(U$2-OUTPUT)") (class "Default")
      (node (ref "C8") (pin "2") (pinfunction "2_2") (pintype "passive"))
      (node (ref "U$2") (pin "P$3") (pinfunction "OUTPUT_P$3") (pintype "bidirectional"))
    )
    (net (code "60") (name "Net-(U$3-G)") (class "Default")
      (node (ref "R14") (pin "1") (pinfunction "1_1") (pintype "passive"))
      (node (ref "R19") (pin "2") (pinfunction "2_2") (pintype "passive"))
      (node (ref "U$3") (pin "1") (pinfunction "G_1") (pintype "bidirectional"))
    )
    (net (code "61") (name "Net-(U$4-G)") (class "Default")
      (node (ref "R21") (pin "1") (pinfunction "1_1") (pintype "passive"))
      (node (ref "R23") (pin "2") (pinfunction "2_2") (pintype "passive"))
      (node (ref "U$4") (pin "1") (pinfunction "G_1") (pintype "bidirectional"))
    )
    (net (code "62") (name "Net-(U$5-G)") (class "Default")
      (node (ref "R25") (pin "1") (pinfunction "1_1") (pintype "passive"))
      (node (ref "R26") (pin "2") (pinfunction "2_2") (pintype "passive"))
      (node (ref "U$5") (pin "1") (pinfunction "G_1") (pintype "bidirectional"))
    )
    (net (code "63") (name "Net-(U$7-G)") (class "Default")
      (node (ref "R28") (pin "1") (pinfunction "1_1") (pintype "passive"))
      (node (ref "R29") (pin "2") (pinfunction "2_2") (pintype "passive"))
      (node (ref "U$7") (pin "1") (pinfunction "G_1") (pintype "bidirectional"))
    )
    (net (code "64") (name "Net-(U$8-G)") (class "Default")
      (node (ref "R32") (pin "1") (pinfunction "1_1") (pintype "passive"))
      (node (ref "R33") (pin "2") (pinfunction "2_2") (pintype "passive"))
      (node (ref "U$8") (pin "1") (pinfunction "G_1") (pintype "bidirectional"))
    )
    (net (code "65") (name "Net-(U$11-C)") (class "Default")
      (node (ref "C5") (pin "1") (pinfunction "1_1") (pintype "passive"))
      (node (ref "U$11") (pin "P$2") (pinfunction "C_P$2") (pintype "passive"))
      (node (ref "U$12") (pin "P$1") (pinfunction "A_P$1") (pintype "passive"))
    )
    (net (code "66") (name "Net-(U$12-C)") (class "Default")
      (node (ref "C4") (pin "2") (pinfunction "2_2") (pintype "passive"))
      (node (ref "U$12") (pin "P$2") (pinfunction "C_P$2") (pintype "passive"))
      (node (ref "U$13") (pin "P$1") (pinfunction "A_P$1") (pintype "passive"))
    )
    (net (code "67") (name "Net-(U$13-C)") (class "Default")
      (node (ref "R4") (pin "2") (pinfunction "2_2") (pintype "passive"))
      (node (ref "R5") (pin "2") (pinfunction "2_2") (pintype "passive"))
      (node (ref "U$13") (pin "P$2") (pinfunction "C_P$2") (pintype "passive"))
      (node (ref "U$14") (pin "P$1") (pinfunction "1_P$1") (pintype "passive"))
    )
    (net (code "68") (name "Net-(U$15-+)") (class "Default")
      (node (ref "R9") (pin "1") (pinfunction "1_1") (pintype "passive"))
      (node (ref "U$15") (pin "P$1") (pinfunction "+_P$1") (pintype "bidirectional"))
    )
    (net (code "69") (name "Net-(U$19-G)") (class "Default")
      (node (ref "R22") (pin "1") (pinfunction "1_1") (pintype "passive"))
      (node (ref "R31") (pin "2") (pinfunction "2_2") (pintype "passive"))
      (node (ref "U$19") (pin "1") (pinfunction "G_1") (pintype "bidirectional"))
    )
    (net (code "70") (name "Net-(U1-PC12)") (class "Default")
      (node (ref "R15") (pin "1") (pinfunction "1_1") (pintype "passive"))
      (node (ref "U1") (pin "53") (pinfunction "PC12_53") (pintype "bidirectional"))
    )
    (net (code "71") (name "Net-(U1-PH0{slash}OSC_IN)") (class "Default")
      (node (ref "C8") (pin "1") (pinfunction "1_1") (pintype "passive"))
      (node (ref "U1") (pin "5") (pinfunction "PH0/OSC_IN_5") (pintype "bidirectional"))
    )
    (net (code "72") (name "Net-(U1-VCAP_1)") (class "Default")
      (node (ref "C9") (pin "2") (pinfunction "2_2") (pintype "passive"))
      (node (ref "U1") (pin "31") (pinfunction "VCAP_1_31") (pintype "power_in"))
    )
    (net (code "73") (name "Net-(U1-VCAP_2)") (class "Default")
      (node (ref "C13") (pin "2") (pinfunction "2_2") (pintype "passive"))
      (node (ref "U1") (pin "47") (pinfunction "VCAP_2_47") (pintype "power_in"))
    )
    (net (code "74") (name "Net-(U2-OUTPUT)") (class "Default")
      (node (ref "R3") (pin "2") (pinfunction "2_2") (pintype "passive"))
      (node (ref "U2") (pin "3") (pinfunction "OUTPUT_3") (pintype "output"))
      (node (ref "VR1") (pin "1") (pinfunction "CCW_1") (pintype "passive"))
    )
    (net (code "75") (name "Net-(U2-THRESHOLD)") (class "Default")
      (node (ref "C1") (pin "2") (pinfunction "2_2") (pintype "passive"))
      (node (ref "R2") (pin "1") (pinfunction "1_1") (pintype "passive"))
      (node (ref "U2") (pin "2") (pinfunction "~{TRIGGER}_2") (pintype "input"))
      (node (ref "U2") (pin "6") (pinfunction "THRESHOLD_6") (pintype "input"))
    )
    (net (code "76") (name "Net-(VR1-CW)") (class "Default")
      (node (ref "R2") (pin "2") (pinfunction "2_2") (pintype "passive"))
      (node (ref "VR1") (pin "2") (pinfunction "WIPER_2") (pintype "passive"))
      (node (ref "VR1") (pin "3") (pinfunction "CW_3") (pintype "passive"))
    )
    (net (code "77") (name "unconnected-(BSK1-Pad8)") (class "Default")
      (node (ref "BSK1") (pin "8") (pinfunction "8_8") (pintype "passive"))
    )
    (net (code "78") (name "unconnected-(R24-Pad1)") (class "Default")
      (node (ref "R24") (pin "1") (pinfunction "1_1") (pintype "passive"))
    )
    (net (code "79") (name "unconnected-(R27-Pad1)") (class "Default")
      (node (ref "R27") (pin "1") (pinfunction "1_1") (pintype "passive"))
    )
    (net (code "80") (name "unconnected-(R30-Pad1)") (class "Default")
      (node (ref "R30") (pin "1") (pinfunction "1_1") (pintype "passive"))
    )
    (net (code "81") (name "unconnected-(U$1-SDO-PadP$2)") (class "Default")
      (node (ref "U$1") (pin "P$2") (pinfunction "SDO_P$2") (pintype "bidirectional"))
    )
    (net (code "82") (name "unconnected-(U$2-STANDBY-PadP$1)") (class "Default")
      (node (ref "U$2") (pin "P$1") (pinfunction "STANDBY_P$1") (pintype "bidirectional"))
    )
    (net (code "83") (name "unconnected-(U$6-PadNC{slash}3V3)") (class "Default")
      (node (ref "U$6") (pin "NC/3V3") (pinfunction "NC/3V3_NC/3V3") (pintype "bidirectional"))
    )
    (net (code "84") (name "unconnected-(U$6-PadNC{slash}GPIO)") (class "Default")
      (node (ref "U$6") (pin "NC/GPIO") (pinfunction "NC/GPIO_NC/GPIO") (pintype "bidirectional"))
    )
    (net (code "85") (name "unconnected-(U$6-PadNC{slash}M1)") (class "Default")
      (node (ref "U$6") (pin "NC/M1") (pinfunction "NC/M1_NC/M1") (pintype "bidirectional"))
    )
    (net (code "86") (name "unconnected-(U1-PA3{slash}USART2_RX-Pad17)") (class "Default")
      (node (ref "U1") (pin "17") (pinfunction "PA3/USART2_RX_17") (pintype "bidirectional"))
    )
    (net (code "87") (name "unconnected-(U1-PA4{slash}USART2_CK-Pad20)") (class "Default")
      (node (ref "U1") (pin "20") (pinfunction "PA4/USART2_CK_20") (pintype "bidirectional"))
    )
    (net (code "88") (name "unconnected-(U1-PA5{slash}SPI1_SCK-Pad21)") (class "Default")
      (node (ref "U1") (pin "21") (pinfunction "PA5/SPI1_SCK_21") (pintype "bidirectional"))
    )
    (net (code "89") (name "unconnected-(U1-PB3-Pad55)") (class "Default")
      (node (ref "U1") (pin "55") (pinfunction "PB3_55") (pintype "bidirectional"))
    )
    (net (code "90") (name "unconnected-(U1-PB4-Pad56)") (class "Default")
      (node (ref "U1") (pin "56") (pinfunction "PB4_56") (pintype "bidirectional"))
    )
    (net (code "91") (name "unconnected-(U1-PB9-Pad62)") (class "Default")
      (node (ref "U1") (pin "62") (pinfunction "PB9_62") (pintype "bidirectional"))
    )
    (net (code "92") (name "unconnected-(U1-PB15-Pad36)") (class "Default")
      (node (ref "U1") (pin "36") (pinfunction "PB15_36") (pintype "bidirectional"))
    )
    (net (code "93") (name "unconnected-(U1-PC3{slash}SPI2_MOSI-Pad11)") (class "Default")
      (node (ref "U1") (pin "11") (pinfunction "PC3/SPI2_MOSI_11") (pintype "bidirectional"))
    )
    (net (code "94") (name "unconnected-(U1-PC4-Pad24)") (class "Default")
      (node (ref "U1") (pin "24") (pinfunction "PC4_24") (pintype "bidirectional"))
    )
    (net (code "95") (name "unconnected-(U1-PC5-Pad25)") (class "Default")
      (node (ref "U1") (pin "25") (pinfunction "PC5_25") (pintype "bidirectional"))
    )
    (net (code "96") (name "unconnected-(U1-PC6-Pad37)") (class "Default")
      (node (ref "U1") (pin "37") (pinfunction "PC6_37") (pintype "bidirectional"))
    )
    (net (code "97") (name "unconnected-(U1-PC7-Pad38)") (class "Default")
      (node (ref "U1") (pin "38") (pinfunction "PC7_38") (pintype "bidirectional"))
    )
    (net (code "98") (name "unconnected-(U1-PC8-Pad39)") (class "Default")
      (node (ref "U1") (pin "39") (pinfunction "PC8_39") (pintype "bidirectional"))
    )
    (net (code "99") (name "unconnected-(U1-PC9-Pad40)") (class "Default")
      (node (ref "U1") (pin "40") (pinfunction "PC9_40") (pintype "bidirectional"))
    )
    (net (code "100") (name "unconnected-(U1-PC13{slash}RTC_OUT-Pad2)") (class "Default")
      (node (ref "U1") (pin "2") (pinfunction "PC13/RTC_OUT_2") (pintype "bidirectional"))
    )
    (net (code "101") (name "unconnected-(U1-PC14{slash}OSC32_IN-Pad3)") (class "Default")
      (node (ref "U1") (pin "3") (pinfunction "PC14/OSC32_IN_3") (pintype "bidirectional"))
    )
    (net (code "102") (name "unconnected-(U1-PC15{slash}OSC32_OUT-Pad4)") (class "Default")
      (node (ref "U1") (pin "4") (pinfunction "PC15/OSC32_OUT_4") (pintype "bidirectional"))
    )
    (net (code "103") (name "unconnected-(U1-PD2-Pad54)") (class "Default")
      (node (ref "U1") (pin "54") (pinfunction "PD2_54") (pintype "bidirectional"))
    )
    (net (code "104") (name "unconnected-(U1-PH1{slash}OSC_OUT-Pad6)") (class "Default")
      (node (ref "U1") (pin "6") (pinfunction "PH1/OSC_OUT_6") (pintype "bidirectional"))
    )
    (net (code "105") (name "unconnected-(U2-CONTROL_VOLTAGE-Pad5)") (class "Default")
      (node (ref "U2") (pin "5") (pinfunction "CONTROL_VOLTAGE_5") (pintype "input"))
    )
    (net (code "106") (name "unconnected-(U2-DISCHARGE-Pad7)") (class "Default")
      (node (ref "U2") (pin "7") (pinfunction "DISCHARGE_7") (pintype "input"))
    )
  )
)
